# 017_SoC_CSI_OLDI.net
KiCad netlist of a schematic drawn in Altium Designer
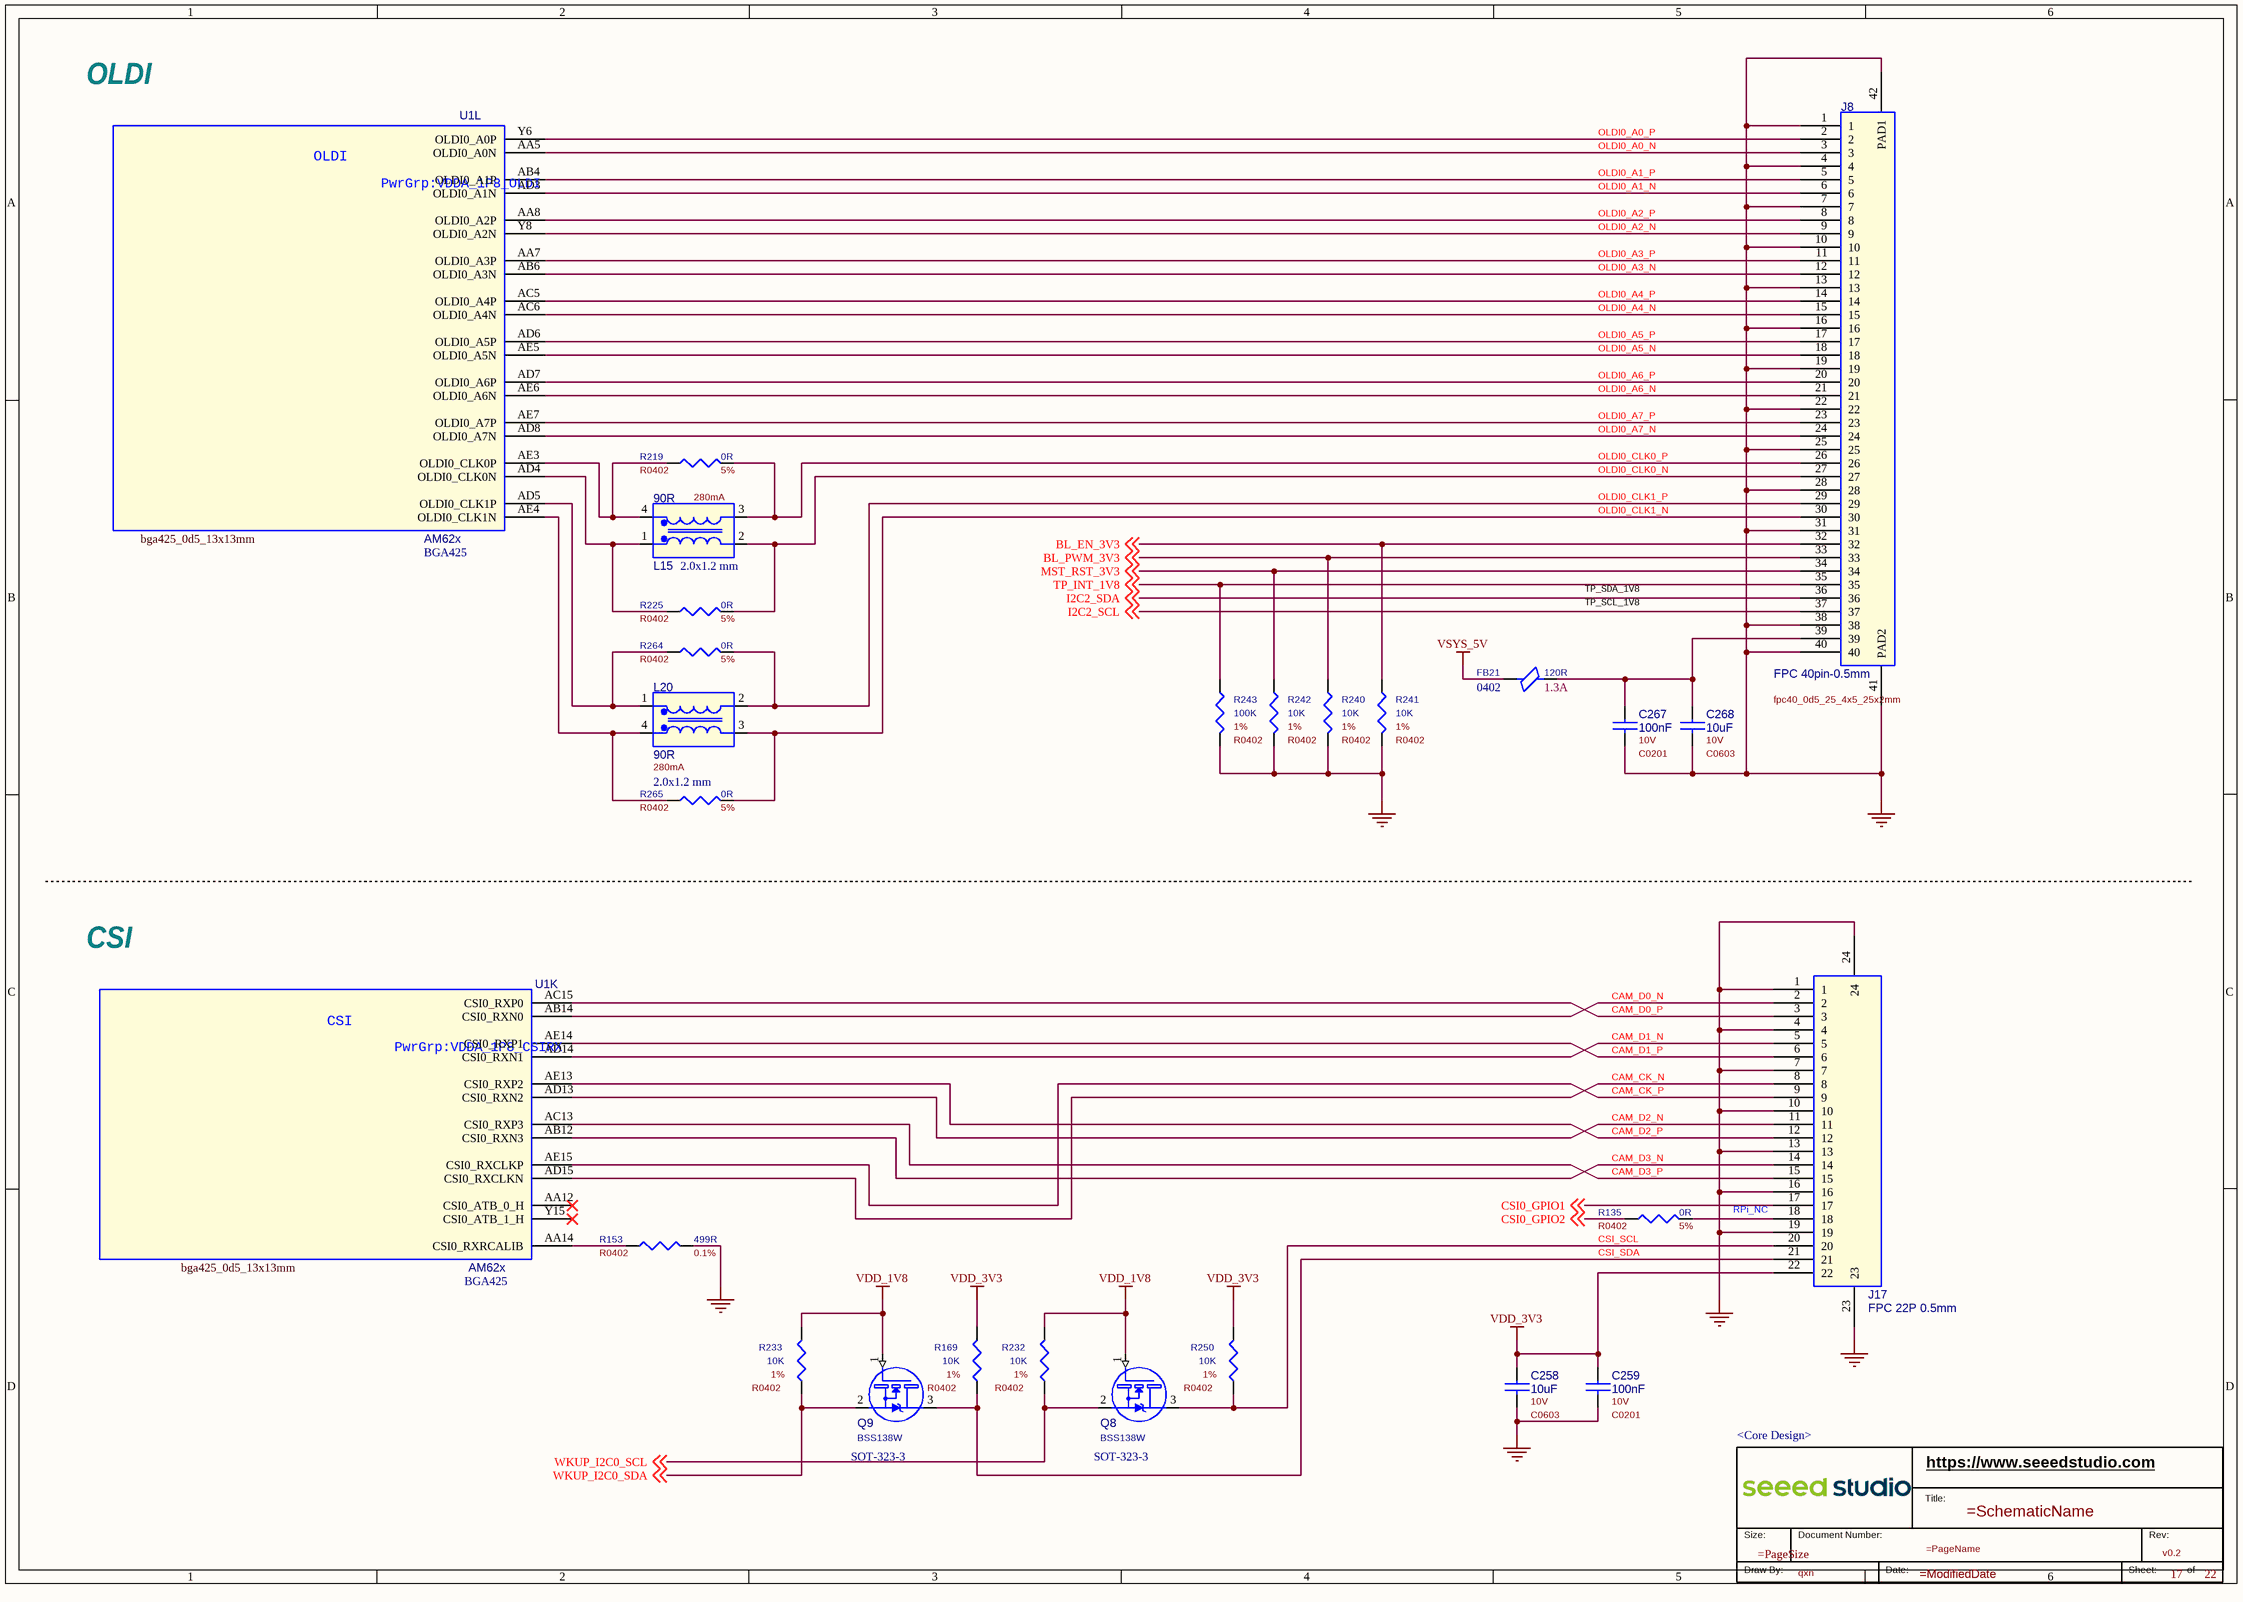
[diagram p0: 017_SoC CSI & OLDI.SchDoc]

(export (version "E")
  (design (tool "Eeschema 10.0.6"))
  (components
    (comp (ref "C258")
      (value "10uF")
      (footprint "C0603")
      (description "CAP, Ceramic, SMD, 10uF, 10%, 10V, 0603")
      (fields
        (field (name "RATING") "10V")
        (field (name "PCB FOOTPRINT") "C0603")
        (field (name "TOLERANCE") "10%")
        (field (name "MANUFACTURER") "YAGEO")
      )
      (libsource (lib "*") (part "CC"))
    )
    (comp (ref "C259")
      (value "100nF")
      (footprint "C0201")
      (description "CAP, Ceramic, SMD, 100nF, 10%, 10V, 0201")
      (fields
        (field (name "RATING") "10V")
        (field (name "PCB FOOTPRINT") "C0201")
        (field (name "TOLERANCE") "10%")
        (field (name "MANUFACTURER PART NUMBER") "CC0201KRX5R6BB104")
      )
      (libsource (lib "*") (part "CC"))
    )
    (comp (ref "C267")
      (value "100nF")
      (footprint "C0201")
      (description "CAP, Ceramic, SMD, 100nF, 10%, 10V, 0201")
      (fields
        (field (name "RATING") "10V")
        (field (name "PCB FOOTPRINT") "C0201")
        (field (name "MANUFACTURER") "YAGEO")
        (field (name "TOLERANCE") "10%")
      )
      (libsource (lib "*") (part "CC"))
    )
    (comp (ref "C268")
      (value "10uF")
      (footprint "C0603")
      (description "CAP, Ceramic, SMD, 10uF, 10%, 10V, 0603")
      (fields
        (field (name "RATING") "10V")
        (field (name "PCB FOOTPRINT") "C0603")
        (field (name "MANUFACTURER") "YAGEO")
        (field (name "TOLERANCE") "10%")
      )
      (libsource (lib "*") (part "CC"))
    )
    (comp (ref "FB21")
      (value "120R")
      (footprint "L0402")
      (description "Ferrite Bead, 120R, , 1.3A, 0402")
      (fields
        (field (name "RATING") "1.3A")
        (field (name "PACKAGE SIZE") "0402")
        (field (name "MANUFACTURER") "Murata")
        (field (name "Comment") "FB")
      )
      (libsource (lib "*") (part "FB"))
    )
    (comp (ref "J8")
      (value "FPC 40pin-0.5mm")
      (footprint "fpc40_0d5_25_4x5_25x2mm")
      (description "CONN, FPC Connectors, 0.5K-DX-40PWB, 40P, SMD")
      (fields
        (field (name "PCB FOOTPRINT") "fpc40_0d5_25_4x5_25x2mm")
        (field (name "MANUFACTURER") "BEST Electronics")
        (field (name "Comment") "Header 40+2P")
      )
      (libsource (lib "*") (part "Header 40+2P"))
    )
    (comp (ref "J17")
      (value "FPC 22P 0.5mm")
      (footprint "fpc22_0d5_15_4x5_25x2mm_0d5_dx_npwb")
      (description "CONN, FPC Connectors, FPC 22P 0.5mm, 22P+2P, SMD")
      (fields
        (field (name "MANUFACTURER PART NUMBER") "0.5K-DX-22PWB")
        (field (name "MANUFACTURER") "BEST Electronics")
      )
      (libsource (lib "*") (part "FPC 22+2P"))
    )
    (comp (ref "L15")
      (value "90R")
      (footprint "L2012")
      (description "Common Mode Filter, 90R, --, 280mA, 2.0x1.2 mm")
      (fields
        (field (name "RATING") "280mA")
        (field (name "PACKAGE SIZE") "2.0x1.2 mm")
        (field (name "MANUFACTURER") "Murata")
        (field (name "Comment") "CL")
      )
      (libsource (lib "") (part "CL_1"))
    )
    (comp (ref "L20")
      (value "90R")
      (footprint "L2012")
      (description "Common Mode Filter, 90R, --, 280mA, 2.0x1.2 mm")
      (fields
        (field (name "RATING") "280mA")
        (field (name "MANUFACTURER") "Murata")
        (field (name "PACKAGE SIZE") "2.0x1.2 mm")
        (field (name "Comment") "CL")
      )
      (libsource (lib "*") (part "CL"))
    )
    (comp (ref "Q8")
      (value "BSS138W")
      (footprint "SOT-323-3")
      (description "XSTR, MOSFET, N-Channel, BSS138W, 50V, 200mA, SOT-323-3, SMD")
      (fields
        (field (name "PACKAGE SIZE") "SOT-323-3")
        (field (name "MANUFACTURER") "Diodes")
        (field (name "Comment") "NMOS_123")
      )
      (libsource (lib "*") (part "NMOS_123"))
    )
    (comp (ref "Q9")
      (value "BSS138W")
      (footprint "SOT-323-3")
      (description "XSTR, MOSFET, N-Channel, BSS138W, 50V, 200mA, SOT-323-3, SMD")
      (fields
        (field (name "PACKAGE SIZE") "SOT-323-3")
        (field (name "MANUFACTURER") "Diodes")
        (field (name "Comment") "NMOS_123")
      )
      (libsource (lib "*") (part "NMOS_123"))
    )
    (comp (ref "R135")
      (value "0R")
      (footprint "R0402")
      (description "RES, Thick Film, 0R, 5%, 1/16W, SMD, 0402")
      (fields
        (field (name "RATING") "5%")
        (field (name "PCB FOOTPRINT") "R0402")
        (field (name "MANUFACTURER PART NUMBER") "RC0201FR-070RL")
        (field (name "MANUFACTURER") "YAGEO")
      )
      (libsource (lib "*") (part "R"))
    )
    (comp (ref "R153")
      (value "499R")
      (footprint "R0402")
      (description "RES, Thick Film, 499R, 0.1%, 1/16W, SMD, 0402")
      (fields
        (field (name "RATING") "0.1%")
        (field (name "PCB FOOTPRINT") "R0402")
        (field (name "MANUFACTURER") "YAGEO")
        (field (name "Comment") "R")
      )
      (libsource (lib "") (part "R_1"))
    )
    (comp (ref "R169")
      (value "10K")
      (footprint "R0402")
      (description "RES, Thick Film, 10K, 1%, 1/16W, SMD, 0402")
      (fields
        (field (name "RATING") "1%")
        (field (name "PCB FOOTPRINT") "R0402")
        (field (name "MANUFACTURER") "YAGEO")
        (field (name "Comment") "R")
      )
      (libsource (lib "*") (part "R"))
    )
    (comp (ref "R219")
      (value "0R")
      (footprint "R0402")
      (description "RES, Thick Film, 0R, 5%, 1/16W, SMD, 0402")
      (fields
        (field (name "RATING") "5%")
        (field (name "PCB FOOTPRINT") "R0402")
        (field (name "MANUFACTURER") "YAGEO")
        (field (name "MANUFACTURER PART NUMBER") "RC0201FR-070RL")
      )
      (libsource (lib "*") (part "R"))
    )
    (comp (ref "R225")
      (value "0R")
      (footprint "R0402")
      (description "RES, Thick Film, 0R, 5%, 1/16W, SMD, 0402")
      (fields
        (field (name "RATING") "5%")
        (field (name "PCB FOOTPRINT") "R0402")
        (field (name "MANUFACTURER") "YAGEO")
        (field (name "MANUFACTURER PART NUMBER") "RC0201FR-070RL")
      )
      (libsource (lib "*") (part "R"))
    )
    (comp (ref "R232")
      (value "10K")
      (footprint "R0402")
      (description "RES, Thick Film, 10K, 1%, 1/16W, SMD, 0402")
      (fields
        (field (name "RATING") "1%")
        (field (name "PCB FOOTPRINT") "R0402")
        (field (name "MANUFACTURER") "YAGEO")
        (field (name "Comment") "R")
      )
      (libsource (lib "*") (part "R"))
    )
    (comp (ref "R233")
      (value "10K")
      (footprint "R0402")
      (description "RES, Thick Film, 10K, 1%, 1/16W, SMD, 0402")
      (fields
        (field (name "RATING") "1%")
        (field (name "PCB FOOTPRINT") "R0402")
        (field (name "MANUFACTURER") "YAGEO")
        (field (name "Comment") "R")
      )
      (libsource (lib "*") (part "R"))
    )
    (comp (ref "R240")
      (value "10K")
      (footprint "R0402")
      (description "RES, Thick Film, 10K, 1%, 1/16W, SMD, 0402")
      (fields
        (field (name "RATING") "1%")
        (field (name "PCB FOOTPRINT") "R0402")
        (field (name "MANUFACTURER PART NUMBER") "RC0201FR-0710KL")
        (field (name "MANUFACTURER") "YAGEO")
      )
      (libsource (lib "*") (part "R"))
    )
    (comp (ref "R241")
      (value "10K")
      (footprint "R0402")
      (description "RES, Thick Film, 10K, 1%, 1/16W, SMD, 0402")
      (fields
        (field (name "RATING") "1%")
        (field (name "PCB FOOTPRINT") "R0402")
        (field (name "MANUFACTURER PART NUMBER") "RC0201FR-0710KL")
        (field (name "MANUFACTURER") "YAGEO")
      )
      (libsource (lib "*") (part "R"))
    )
    (comp (ref "R242")
      (value "10K")
      (footprint "R0402")
      (description "RES, Thick Film, 10K, 1%, 1/16W, SMD, 0402")
      (fields
        (field (name "RATING") "1%")
        (field (name "PCB FOOTPRINT") "R0402")
        (field (name "MANUFACTURER PART NUMBER") "RC0201FR-0710KL")
        (field (name "MANUFACTURER") "YAGEO")
      )
      (libsource (lib "*") (part "R"))
    )
    (comp (ref "R243")
      (value "100K")
      (footprint "R0402")
      (description "RES, Thick Film, 100K, 1%, 1/16W, SMD, 0402")
      (fields
        (field (name "RATING") "1%")
        (field (name "PCB FOOTPRINT") "R0402")
        (field (name "MANUFACTURER PART NUMBER") "RC0201FR-0710KL")
        (field (name "MANUFACTURER") "YAGEO")
      )
      (libsource (lib "*") (part "R"))
    )
    (comp (ref "R250")
      (value "10K")
      (footprint "R0402")
      (description "RES, Thick Film, 10K, 1%, 1/16W, SMD, 0402")
      (fields
        (field (name "RATING") "1%")
        (field (name "PCB FOOTPRINT") "R0402")
        (field (name "MANUFACTURER") "YAGEO")
        (field (name "Comment") "R")
      )
      (libsource (lib "*") (part "R"))
    )
    (comp (ref "R264")
      (value "0R")
      (footprint "R0402")
      (description "RES, Thick Film, 0R, 5%, 1/16W, SMD, 0402")
      (fields
        (field (name "RATING") "5%")
        (field (name "PCB FOOTPRINT") "R0402")
        (field (name "MANUFACTURER") "YAGEO")
        (field (name "MANUFACTURER PART NUMBER") "RC0201FR-070RL")
      )
      (libsource (lib "*") (part "R"))
    )
    (comp (ref "R265")
      (value "0R")
      (footprint "R0402")
      (description "RES, Thick Film, 0R, 5%, 1/16W, SMD, 0402")
      (fields
        (field (name "RATING") "5%")
        (field (name "PCB FOOTPRINT") "R0402")
        (field (name "MANUFACTURER") "YAGEO")
        (field (name "MANUFACTURER PART NUMBER") "RC0201FR-070RL")
      )
      (libsource (lib "*") (part "R"))
    )
    (comp (ref "U1")
      (value "AM62x")
      (footprint "bga425_0d5_13x13mm")
      (description "IC, Controller, MPU, AM62x, BGA425")
      (fields
        (field (name "PCB FOOTPRINT") "bga425_0d5_13x13mm")
        (field (name "MANUFACTURER") "TI")
        (field (name "PACKAGE SIZE") "BGA425")
        (field (name "Comment") "AM62x_BGA425")
      )
      (libsource (lib "*") (part "AM62x_BGA425"))
    )
  )
  (nets
    (net (code "1") (name "/CAM_CK_N") (class "Default")
      (node (ref "J17") (pin "8") (pinfunction "8_8") (pintype "passive"))
      (node (ref "U1") (pin "AD15") (pinfunction "CSI0_RXCLKN_AD15") (pintype "passive"))
    )
    (net (code "2") (name "/CAM_CK_P") (class "Default")
      (node (ref "J17") (pin "9") (pinfunction "9_9") (pintype "passive"))
      (node (ref "U1") (pin "AE15") (pinfunction "CSI0_RXCLKP_AE15") (pintype "passive"))
    )
    (net (code "3") (name "/CAM_D0_N") (class "Default")
      (node (ref "J17") (pin "2") (pinfunction "2_2") (pintype "passive"))
      (node (ref "U1") (pin "AB14") (pinfunction "CSI0_RXN0_AB14") (pintype "passive"))
    )
    (net (code "4") (name "/CAM_D0_P") (class "Default")
      (node (ref "J17") (pin "3") (pinfunction "3_3") (pintype "passive"))
      (node (ref "U1") (pin "AC15") (pinfunction "CSI0_RXP0_AC15") (pintype "passive"))
    )
    (net (code "5") (name "/CAM_D1_N") (class "Default")
      (node (ref "J17") (pin "5") (pinfunction "5_5") (pintype "passive"))
      (node (ref "U1") (pin "AD14") (pinfunction "CSI0_RXN1_AD14") (pintype "passive"))
    )
    (net (code "6") (name "/CAM_D1_P") (class "Default")
      (node (ref "J17") (pin "6") (pinfunction "6_6") (pintype "passive"))
      (node (ref "U1") (pin "AE14") (pinfunction "CSI0_RXP1_AE14") (pintype "passive"))
    )
    (net (code "7") (name "/CAM_D2_N") (class "Default")
      (node (ref "J17") (pin "11") (pinfunction "11_11") (pintype "passive"))
      (node (ref "U1") (pin "AD13") (pinfunction "CSI0_RXN2_AD13") (pintype "passive"))
    )
    (net (code "8") (name "/CAM_D2_P") (class "Default")
      (node (ref "J17") (pin "12") (pinfunction "12_12") (pintype "passive"))
      (node (ref "U1") (pin "AE13") (pinfunction "CSI0_RXP2_AE13") (pintype "passive"))
    )
    (net (code "9") (name "/CAM_D3_N") (class "Default")
      (node (ref "J17") (pin "14") (pinfunction "14_14") (pintype "passive"))
      (node (ref "U1") (pin "AB12") (pinfunction "CSI0_RXN3_AB12") (pintype "passive"))
    )
    (net (code "10") (name "/CAM_D3_P") (class "Default")
      (node (ref "J17") (pin "15") (pinfunction "15_15") (pintype "passive"))
      (node (ref "U1") (pin "AC13") (pinfunction "CSI0_RXP3_AC13") (pintype "passive"))
    )
    (net (code "11") (name "/CSI_SCL") (class "Default")
      (node (ref "J17") (pin "20") (pinfunction "20_20") (pintype "passive"))
      (node (ref "Q8") (pin "3") (pinfunction "D_3") (pintype "passive"))
      (node (ref "R250") (pin "2") (pinfunction "2_2") (pintype "passive"))
    )
    (net (code "12") (name "/CSI_SDA") (class "Default")
      (node (ref "J17") (pin "21") (pinfunction "21_21") (pintype "passive"))
      (node (ref "Q9") (pin "3") (pinfunction "D_3") (pintype "passive"))
      (node (ref "R169") (pin "2") (pinfunction "2_2") (pintype "passive"))
    )
    (net (code "13") (name "/OLDI0_A0_N") (class "Default")
      (node (ref "J8") (pin "3") (pinfunction "3_3") (pintype "passive"))
      (node (ref "U1") (pin "AA5") (pinfunction "OLDI0_A0N_AA5") (pintype "passive"))
    )
    (net (code "14") (name "/OLDI0_A0_P") (class "Default")
      (node (ref "J8") (pin "2") (pinfunction "2_2") (pintype "passive"))
      (node (ref "U1") (pin "Y6") (pinfunction "OLDI0_A0P_Y6") (pintype "passive"))
    )
    (net (code "15") (name "/OLDI0_A1_N") (class "Default")
      (node (ref "J8") (pin "6") (pinfunction "6_6") (pintype "passive"))
      (node (ref "U1") (pin "AD3") (pinfunction "OLDI0_A1N_AD3") (pintype "passive"))
    )
    (net (code "16") (name "/OLDI0_A1_P") (class "Default")
      (node (ref "J8") (pin "5") (pinfunction "5_5") (pintype "passive"))
      (node (ref "U1") (pin "AB4") (pinfunction "OLDI0_A1P_AB4") (pintype "passive"))
    )
    (net (code "17") (name "/OLDI0_A2_N") (class "Default")
      (node (ref "J8") (pin "9") (pinfunction "9_9") (pintype "passive"))
      (node (ref "U1") (pin "Y8") (pinfunction "OLDI0_A2N_Y8") (pintype "passive"))
    )
    (net (code "18") (name "/OLDI0_A2_P") (class "Default")
      (node (ref "J8") (pin "8") (pinfunction "8_8") (pintype "passive"))
      (node (ref "U1") (pin "AA8") (pinfunction "OLDI0_A2P_AA8") (pintype "passive"))
    )
    (net (code "19") (name "/OLDI0_A3_N") (class "Default")
      (node (ref "J8") (pin "12") (pinfunction "12_12") (pintype "passive"))
      (node (ref "U1") (pin "AB6") (pinfunction "OLDI0_A3N_AB6") (pintype "passive"))
    )
    (net (code "20") (name "/OLDI0_A3_P") (class "Default")
      (node (ref "J8") (pin "11") (pinfunction "11_11") (pintype "passive"))
      (node (ref "U1") (pin "AA7") (pinfunction "OLDI0_A3P_AA7") (pintype "passive"))
    )
    (net (code "21") (name "/OLDI0_A4_N") (class "Default")
      (node (ref "J8") (pin "15") (pinfunction "15_15") (pintype "passive"))
      (node (ref "U1") (pin "AC6") (pinfunction "OLDI0_A4N_AC6") (pintype "passive"))
    )
    (net (code "22") (name "/OLDI0_A4_P") (class "Default")
      (node (ref "J8") (pin "14") (pinfunction "14_14") (pintype "passive"))
      (node (ref "U1") (pin "AC5") (pinfunction "OLDI0_A4P_AC5") (pintype "passive"))
    )
    (net (code "23") (name "/OLDI0_A5_N") (class "Default")
      (node (ref "J8") (pin "18") (pinfunction "18_18") (pintype "passive"))
      (node (ref "U1") (pin "AE5") (pinfunction "OLDI0_A5N_AE5") (pintype "passive"))
    )
    (net (code "24") (name "/OLDI0_A5_P") (class "Default")
      (node (ref "J8") (pin "17") (pinfunction "17_17") (pintype "passive"))
      (node (ref "U1") (pin "AD6") (pinfunction "OLDI0_A5P_AD6") (pintype "passive"))
    )
    (net (code "25") (name "/OLDI0_A6_N") (class "Default")
      (node (ref "J8") (pin "21") (pinfunction "21_21") (pintype "passive"))
      (node (ref "U1") (pin "AE6") (pinfunction "OLDI0_A6N_AE6") (pintype "passive"))
    )
    (net (code "26") (name "/OLDI0_A6_P") (class "Default")
      (node (ref "J8") (pin "20") (pinfunction "20_20") (pintype "passive"))
      (node (ref "U1") (pin "AD7") (pinfunction "OLDI0_A6P_AD7") (pintype "passive"))
    )
    (net (code "27") (name "/OLDI0_A7_N") (class "Default")
      (node (ref "J8") (pin "24") (pinfunction "24_24") (pintype "passive"))
      (node (ref "U1") (pin "AD8") (pinfunction "OLDI0_A7N_AD8") (pintype "passive"))
    )
    (net (code "28") (name "/OLDI0_A7_P") (class "Default")
      (node (ref "J8") (pin "23") (pinfunction "23_23") (pintype "passive"))
      (node (ref "U1") (pin "AE7") (pinfunction "OLDI0_A7P_AE7") (pintype "passive"))
    )
    (net (code "29") (name "/OLDI0_CLK0_N") (class "Default")
      (node (ref "J8") (pin "27") (pinfunction "27_27") (pintype "passive"))
      (node (ref "L15") (pin "2") (pinfunction "2_2") (pintype "passive"))
      (node (ref "R225") (pin "2") (pinfunction "2_2") (pintype "passive"))
    )
    (net (code "30") (name "/OLDI0_CLK0_P") (class "Default")
      (node (ref "J8") (pin "26") (pinfunction "26_26") (pintype "passive"))
      (node (ref "L15") (pin "3") (pinfunction "3_3") (pintype "passive"))
      (node (ref "R219") (pin "2") (pinfunction "2_2") (pintype "passive"))
    )
    (net (code "31") (name "/OLDI0_CLK1_N") (class "Default")
      (node (ref "J8") (pin "30") (pinfunction "30_30") (pintype "passive"))
      (node (ref "L20") (pin "3") (pinfunction "3_3") (pintype "passive"))
      (node (ref "R265") (pin "2") (pinfunction "2_2") (pintype "passive"))
    )
    (net (code "32") (name "/OLDI0_CLK1_P") (class "Default")
      (node (ref "J8") (pin "29") (pinfunction "29_29") (pintype "passive"))
      (node (ref "L20") (pin "2") (pinfunction "2_2") (pintype "passive"))
      (node (ref "R264") (pin "2") (pinfunction "2_2") (pintype "passive"))
    )
    (net (code "33") (name "BL_EN_3V3") (class "Default")
      (node (ref "J8") (pin "32") (pinfunction "32_32") (pintype "passive"))
      (node (ref "R241") (pin "1") (pinfunction "1_1") (pintype "passive"))
    )
    (net (code "34") (name "BL_PWM_3V3") (class "Default")
      (node (ref "J8") (pin "33") (pinfunction "33_33") (pintype "passive"))
      (node (ref "R240") (pin "1") (pinfunction "1_1") (pintype "passive"))
    )
    (net (code "35") (name "CSI0_GPIO1") (class "Default")
      (node (ref "J17") (pin "17") (pinfunction "17_17") (pintype "passive"))
    )
    (net (code "36") (name "CSI0_GPIO2") (class "Default")
      (node (ref "R135") (pin "1") (pinfunction "1_1") (pintype "passive"))
    )
    (net (code "37") (name "GND") (class "Default")
      (node (ref "C258") (pin "2") (pinfunction "2_2") (pintype "passive"))
      (node (ref "C259") (pin "2") (pinfunction "2_2") (pintype "passive"))
      (node (ref "C267") (pin "2") (pinfunction "2_2") (pintype "passive"))
      (node (ref "C268") (pin "2") (pinfunction "2_2") (pintype "passive"))
      (node (ref "J17") (pin "1") (pinfunction "1_1") (pintype "passive"))
      (node (ref "J17") (pin "10") (pinfunction "10_10") (pintype "passive"))
      (node (ref "J17") (pin "13") (pinfunction "13_13") (pintype "passive"))
      (node (ref "J17") (pin "16") (pinfunction "16_16") (pintype "passive"))
      (node (ref "J17") (pin "19") (pinfunction "19_19") (pintype "passive"))
      (node (ref "J17") (pin "23") (pinfunction "23_23") (pintype "passive"))
      (node (ref "J17") (pin "24") (pinfunction "24_24") (pintype "passive"))
      (node (ref "J17") (pin "4") (pinfunction "4_4") (pintype "passive"))
      (node (ref "J17") (pin "7") (pinfunction "7_7") (pintype "passive"))
      (node (ref "J8") (pin "1") (pinfunction "1_1") (pintype "passive"))
      (node (ref "J8") (pin "10") (pinfunction "10_10") (pintype "passive"))
      (node (ref "J8") (pin "13") (pinfunction "13_13") (pintype "passive"))
      (node (ref "J8") (pin "16") (pinfunction "16_16") (pintype "passive"))
      (node (ref "J8") (pin "19") (pinfunction "19_19") (pintype "passive"))
      (node (ref "J8") (pin "22") (pinfunction "22_22") (pintype "passive"))
      (node (ref "J8") (pin "25") (pinfunction "25_25") (pintype "passive"))
      (node (ref "J8") (pin "28") (pinfunction "28_28") (pintype "passive"))
      (node (ref "J8") (pin "31") (pinfunction "31_31") (pintype "passive"))
      (node (ref "J8") (pin "38") (pinfunction "38_38") (pintype "passive"))
      (node (ref "J8") (pin "4") (pinfunction "4_4") (pintype "passive"))
      (node (ref "J8") (pin "40") (pinfunction "40_40") (pintype "passive"))
      (node (ref "J8") (pin "41") (pinfunction "PAD2_41") (pintype "passive"))
      (node (ref "J8") (pin "42") (pinfunction "PAD1_42") (pintype "passive"))
      (node (ref "J8") (pin "7") (pinfunction "7_7") (pintype "passive"))
      (node (ref "R153") (pin "2") (pinfunction "2_2") (pintype "passive"))
      (node (ref "R240") (pin "2") (pinfunction "2_2") (pintype "passive"))
      (node (ref "R241") (pin "2") (pinfunction "2_2") (pintype "passive"))
      (node (ref "R242") (pin "2") (pinfunction "2_2") (pintype "passive"))
      (node (ref "R243") (pin "2") (pinfunction "2_2") (pintype "passive"))
    )
    (net (code "38") (name "I2C2_SCL") (class "Default")
      (node (ref "J8") (pin "37") (pinfunction "37_37") (pintype "passive"))
    )
    (net (code "39") (name "I2C2_SDA") (class "Default")
      (node (ref "J8") (pin "36") (pinfunction "36_36") (pintype "passive"))
    )
    (net (code "40") (name "MST_RST_3V3") (class "Default")
      (node (ref "J8") (pin "34") (pinfunction "34_34") (pintype "passive"))
      (node (ref "R242") (pin "1") (pinfunction "1_1") (pintype "passive"))
    )
    (net (code "41") (name "Net-(C267-Pad1)") (class "Default")
      (node (ref "C267") (pin "1") (pinfunction "1_1") (pintype "passive"))
      (node (ref "C268") (pin "1") (pinfunction "1_1") (pintype "passive"))
      (node (ref "FB21") (pin "2") (pinfunction "2_2") (pintype "passive"))
      (node (ref "J8") (pin "39") (pinfunction "39_39") (pintype "passive"))
    )
    (net (code "42") (name "Net-(J17-Pad18)") (class "Default")
      (node (ref "J17") (pin "18") (pinfunction "18_18") (pintype "passive"))
      (node (ref "R135") (pin "2") (pinfunction "2_2") (pintype "passive"))
    )
    (net (code "43") (name "Net-(U1K-CSI0_RXRCALIB)") (class "Default")
      (node (ref "R153") (pin "1") (pinfunction "1_1") (pintype "passive"))
      (node (ref "U1") (pin "AA14") (pinfunction "CSI0_RXRCALIB_AA14") (pintype "passive"))
    )
    (net (code "44") (name "Net-(U1L-OLDI0_CLK0N)") (class "Default")
      (node (ref "L15") (pin "1") (pinfunction "1_1") (pintype "passive"))
      (node (ref "R225") (pin "1") (pinfunction "1_1") (pintype "passive"))
      (node (ref "U1") (pin "AD4") (pinfunction "OLDI0_CLK0N_AD4") (pintype "passive"))
    )
    (net (code "45") (name "Net-(U1L-OLDI0_CLK0P)") (class "Default")
      (node (ref "L15") (pin "4") (pinfunction "4_4") (pintype "passive"))
      (node (ref "R219") (pin "1") (pinfunction "1_1") (pintype "passive"))
      (node (ref "U1") (pin "AE3") (pinfunction "OLDI0_CLK0P_AE3") (pintype "passive"))
    )
    (net (code "46") (name "Net-(U1L-OLDI0_CLK1N)") (class "Default")
      (node (ref "L20") (pin "4") (pinfunction "4_4") (pintype "passive"))
      (node (ref "R265") (pin "1") (pinfunction "1_1") (pintype "passive"))
      (node (ref "U1") (pin "AE4") (pinfunction "OLDI0_CLK1N_AE4") (pintype "passive"))
    )
    (net (code "47") (name "Net-(U1L-OLDI0_CLK1P)") (class "Default")
      (node (ref "L20") (pin "1") (pinfunction "1_1") (pintype "passive"))
      (node (ref "R264") (pin "1") (pinfunction "1_1") (pintype "passive"))
      (node (ref "U1") (pin "AD5") (pinfunction "OLDI0_CLK1P_AD5") (pintype "passive"))
    )
    (net (code "48") (name "TP_INT_1V8") (class "Default")
      (node (ref "J8") (pin "35") (pinfunction "35_35") (pintype "passive"))
      (node (ref "R243") (pin "1") (pinfunction "1_1") (pintype "passive"))
    )
    (net (code "49") (name "VDD_1V8") (class "Default")
      (node (ref "Q8") (pin "1") (pinfunction "G_1") (pintype "input"))
      (node (ref "Q9") (pin "1") (pinfunction "G_1") (pintype "input"))
      (node (ref "R232") (pin "1") (pinfunction "1_1") (pintype "passive"))
      (node (ref "R233") (pin "1") (pinfunction "1_1") (pintype "passive"))
    )
    (net (code "50") (name "VDD_3V3") (class "Default")
      (node (ref "C258") (pin "1") (pinfunction "1_1") (pintype "passive"))
      (node (ref "C259") (pin "1") (pinfunction "1_1") (pintype "passive"))
      (node (ref "J17") (pin "22") (pinfunction "22_22") (pintype "passive"))
      (node (ref "R169") (pin "1") (pinfunction "1_1") (pintype "passive"))
      (node (ref "R250") (pin "1") (pinfunction "1_1") (pintype "passive"))
    )
    (net (code "51") (name "VSYS_5V") (class "Default")
      (node (ref "FB21") (pin "1") (pinfunction "1_1") (pintype "passive"))
    )
    (net (code "52") (name "WKUP_I2C0_SCL") (class "Default")
      (node (ref "Q8") (pin "2") (pinfunction "S_2") (pintype "passive"))
      (node (ref "R232") (pin "2") (pinfunction "2_2") (pintype "passive"))
    )
    (net (code "53") (name "WKUP_I2C0_SDA") (class "Default")
      (node (ref "Q9") (pin "2") (pinfunction "S_2") (pintype "passive"))
      (node (ref "R233") (pin "2") (pinfunction "2_2") (pintype "passive"))
    )
    (net (code "54") (name "unconnected-(U1K-CSI0_ATB_0_H-PadAA12)") (class "Default")
      (node (ref "U1") (pin "AA12") (pinfunction "CSI0_ATB_0_H_AA12") (pintype "passive+no_connect"))
    )
    (net (code "55") (name "unconnected-(U1K-CSI0_ATB_1_H-PadY15)") (class "Default")
      (node (ref "U1") (pin "Y15") (pinfunction "CSI0_ATB_1_H_Y15") (pintype "passive+no_connect"))
    )
  )
)
